# osbee_shield_1_0.net
KiCad netlist of a schematic drawn in EAGLE
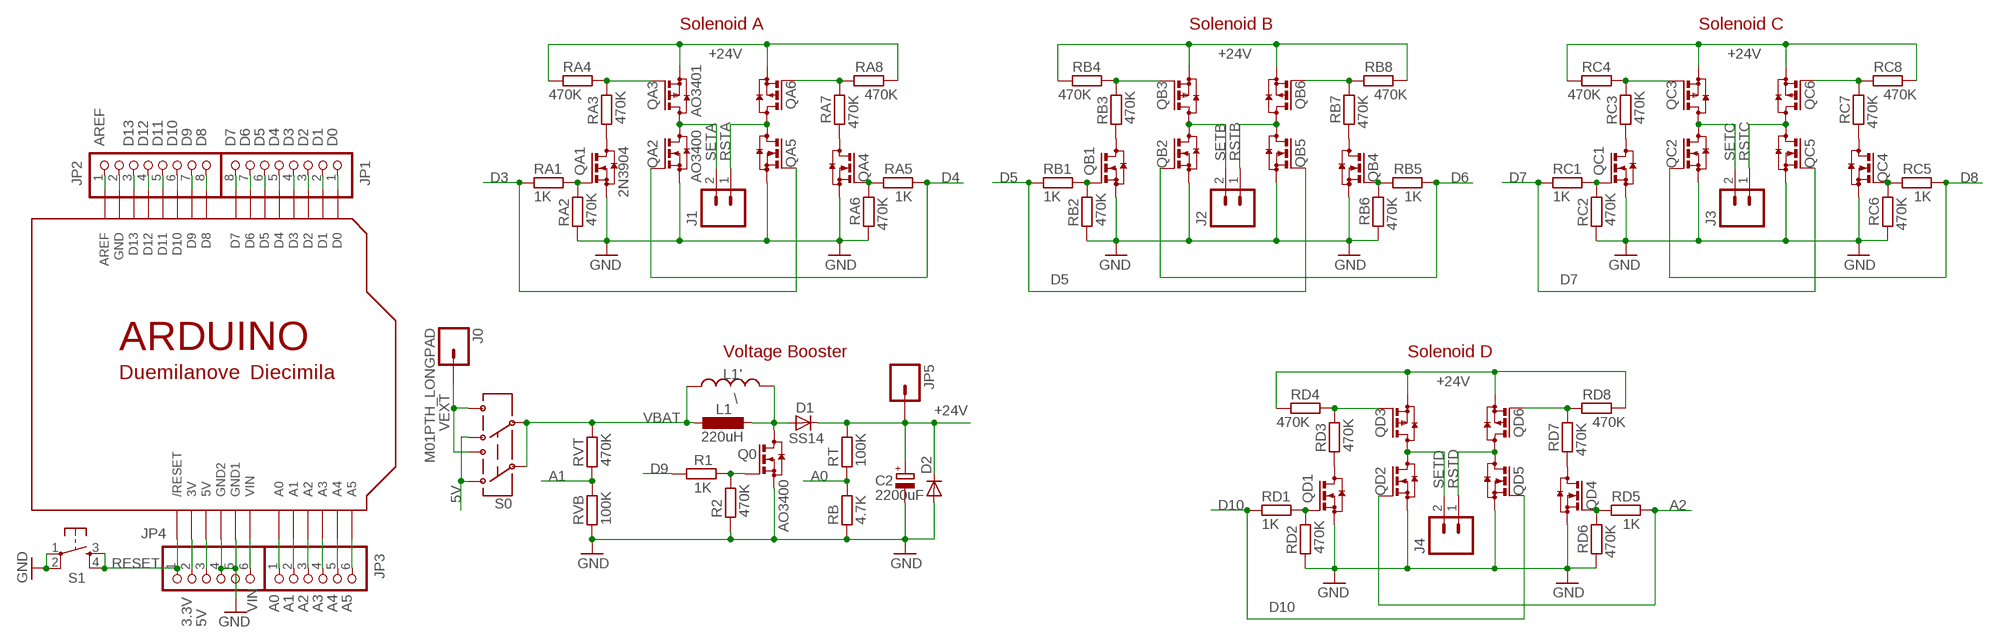
[diagram p0: schematic, sheet 1]

(export (version "E")
  (design (tool "Eeschema 10.0.6"))
  (components
    (comp (ref "C2")
      (value "2200uF")
      (footprint "eagle-import:E5-13")
      (libsource (lib "eagle-import") (part "CPOL-EUE5-13"))
    )
    (comp (ref "D1")
      (value "SS14")
      (footprint "eagle-import:DO-214AC")
      (libsource (lib "eagle-import") (part "DIODE-DO-214AC"))
    )
    (comp (ref "D2")
      (value "DIODE-MINIMELF")
      (footprint "eagle-import:MINIMELF")
      (libsource (lib "eagle-import") (part "DIODE-MINIMELF"))
    )
    (comp (ref "J0")
      (value "M01PTH_LONGPAD")
      (footprint "eagle-import:1X01_LONGPAD")
      (libsource (lib "eagle-import") (part "M01PTH_LONGPAD"))
    )
    (comp (ref "J1")
      (value "M025MM")
      (footprint "eagle-import:SCREWTERMINAL-5MM-2")
      (libsource (lib "eagle-import") (part "M025MM"))
    )
    (comp (ref "J2")
      (value "M025MM")
      (footprint "eagle-import:SCREWTERMINAL-5MM-2")
      (libsource (lib "eagle-import") (part "M025MM"))
    )
    (comp (ref "J3")
      (value "M025MM")
      (footprint "eagle-import:SCREWTERMINAL-5MM-2")
      (libsource (lib "eagle-import") (part "M025MM"))
    )
    (comp (ref "J4")
      (value "M025MM")
      (footprint "eagle-import:SCREWTERMINAL-5MM-2")
      (libsource (lib "eagle-import") (part "M025MM"))
    )
    (comp (ref "JP1")
      (value "PINHD-1X8BIG")
      (footprint "eagle-import:1X08-BIG")
      (libsource (lib "eagle-import") (part "PINHD-1X8BIG"))
    )
    (comp (ref "JP2")
      (value "PINHD-1X8BIG")
      (footprint "eagle-import:1X08-BIG")
      (libsource (lib "eagle-import") (part "PINHD-1X8BIG"))
    )
    (comp (ref "JP3")
      (value "PINHD-1X6B")
      (footprint "eagle-import:1X06-BIG")
      (libsource (lib "eagle-import") (part "PINHD-1X6B"))
    )
    (comp (ref "JP4")
      (value "PINHD-1X6B")
      (footprint "eagle-import:1X06-BIG")
      (libsource (lib "eagle-import") (part "PINHD-1X6B"))
    )
    (comp (ref "JP5")
      (value "M01SMDNS")
      (footprint "eagle-import:1X01NS")
      (libsource (lib "eagle-import") (part "M01SMDNS"))
    )
    (comp (ref "L1")
      (value "220uH")
      (footprint "eagle-import:0204_5")
      (libsource (lib "eagle-import") (part "L-EU0204/5"))
    )
    (comp (ref "L1'")
      (value "\\")
      (footprint "eagle-import:INDUCTOR_D58")
      (libsource (lib "eagle-import") (part "INDUCTOR_SMDD58"))
    )
    (comp (ref "Q0")
      (value "AO3400")
      (footprint "eagle-import:SOT23")
      (libsource (lib "eagle-import") (part "BSS123"))
    )
    (comp (ref "QA1")
      (value "2N3904")
      (footprint "eagle-import:SOT23")
      (libsource (lib "eagle-import") (part "BSS123"))
    )
    (comp (ref "QA2")
      (value "AO3400")
      (footprint "eagle-import:SOT23")
      (libsource (lib "eagle-import") (part "BSS123"))
    )
    (comp (ref "QA3")
      (value "AO3401")
      (footprint "eagle-import:SOT23")
      (libsource (lib "eagle-import") (part "BSS84"))
    )
    (comp (ref "QA4")
      (value "BSS123")
      (footprint "eagle-import:SOT23")
      (libsource (lib "eagle-import") (part "BSS123"))
    )
    (comp (ref "QA5")
      (value "BSS123")
      (footprint "eagle-import:SOT23")
      (libsource (lib "eagle-import") (part "BSS123"))
    )
    (comp (ref "QA6")
      (value "BSS84")
      (footprint "eagle-import:SOT23")
      (libsource (lib "eagle-import") (part "BSS84"))
    )
    (comp (ref "QB1")
      (value "BSS123")
      (footprint "eagle-import:SOT23")
      (libsource (lib "eagle-import") (part "BSS123"))
    )
    (comp (ref "QB2")
      (value "BSS123")
      (footprint "eagle-import:SOT23")
      (libsource (lib "eagle-import") (part "BSS123"))
    )
    (comp (ref "QB3")
      (value "BSS84")
      (footprint "eagle-import:SOT23")
      (libsource (lib "eagle-import") (part "BSS84"))
    )
    (comp (ref "QB4")
      (value "BSS123")
      (footprint "eagle-import:SOT23")
      (libsource (lib "eagle-import") (part "BSS123"))
    )
    (comp (ref "QB5")
      (value "BSS123")
      (footprint "eagle-import:SOT23")
      (libsource (lib "eagle-import") (part "BSS123"))
    )
    (comp (ref "QB6")
      (value "BSS84")
      (footprint "eagle-import:SOT23")
      (libsource (lib "eagle-import") (part "BSS84"))
    )
    (comp (ref "QC1")
      (value "BSS123")
      (footprint "eagle-import:SOT23")
      (libsource (lib "eagle-import") (part "BSS123"))
    )
    (comp (ref "QC2")
      (value "BSS123")
      (footprint "eagle-import:SOT23")
      (libsource (lib "eagle-import") (part "BSS123"))
    )
    (comp (ref "QC3")
      (value "BSS84")
      (footprint "eagle-import:SOT23")
      (libsource (lib "eagle-import") (part "BSS84"))
    )
    (comp (ref "QC4")
      (value "BSS123")
      (footprint "eagle-import:SOT23")
      (libsource (lib "eagle-import") (part "BSS123"))
    )
    (comp (ref "QC5")
      (value "BSS123")
      (footprint "eagle-import:SOT23")
      (libsource (lib "eagle-import") (part "BSS123"))
    )
    (comp (ref "QC6")
      (value "BSS84")
      (footprint "eagle-import:SOT23")
      (libsource (lib "eagle-import") (part "BSS84"))
    )
    (comp (ref "QD1")
      (value "BSS123")
      (footprint "eagle-import:SOT23")
      (libsource (lib "eagle-import") (part "BSS123"))
    )
    (comp (ref "QD2")
      (value "BSS123")
      (footprint "eagle-import:SOT23")
      (libsource (lib "eagle-import") (part "BSS123"))
    )
    (comp (ref "QD3")
      (value "BSS84")
      (footprint "eagle-import:SOT23")
      (libsource (lib "eagle-import") (part "BSS84"))
    )
    (comp (ref "QD4")
      (value "BSS123")
      (footprint "eagle-import:SOT23")
      (libsource (lib "eagle-import") (part "BSS123"))
    )
    (comp (ref "QD5")
      (value "BSS123")
      (footprint "eagle-import:SOT23")
      (libsource (lib "eagle-import") (part "BSS123"))
    )
    (comp (ref "QD6")
      (value "BSS84")
      (footprint "eagle-import:SOT23")
      (libsource (lib "eagle-import") (part "BSS84"))
    )
    (comp (ref "R1")
      (value "1K")
      (footprint "eagle-import:R0805")
      (libsource (lib "eagle-import") (part "R-EU_R0805"))
    )
    (comp (ref "R2")
      (value "470K")
      (footprint "eagle-import:R0805")
      (libsource (lib "eagle-import") (part "R-EU_R0805"))
    )
    (comp (ref "RA1")
      (value "1K")
      (footprint "eagle-import:R0805")
      (libsource (lib "eagle-import") (part "R-EU_R0805"))
    )
    (comp (ref "RA2")
      (value "470K")
      (footprint "eagle-import:R0805")
      (libsource (lib "eagle-import") (part "R-EU_R0805"))
    )
    (comp (ref "RA3")
      (value "470K")
      (footprint "eagle-import:R0805")
      (libsource (lib "eagle-import") (part "R-EU_R0805"))
    )
    (comp (ref "RA4")
      (value "470K")
      (footprint "eagle-import:R0805")
      (libsource (lib "eagle-import") (part "R-EU_R0805"))
    )
    (comp (ref "RA5")
      (value "1K")
      (footprint "eagle-import:R0805")
      (libsource (lib "eagle-import") (part "R-EU_R0805"))
    )
    (comp (ref "RA6")
      (value "470K")
      (footprint "eagle-import:R0805")
      (libsource (lib "eagle-import") (part "R-EU_R0805"))
    )
    (comp (ref "RA7")
      (value "470K")
      (footprint "eagle-import:R0805")
      (libsource (lib "eagle-import") (part "R-EU_R0805"))
    )
    (comp (ref "RA8")
      (value "470K")
      (footprint "eagle-import:R0805")
      (libsource (lib "eagle-import") (part "R-EU_R0805"))
    )
    (comp (ref "RB")
      (value "4.7K")
      (footprint "eagle-import:R0805")
      (libsource (lib "eagle-import") (part "R-EU_R0805"))
    )
    (comp (ref "RB1")
      (value "1K")
      (footprint "eagle-import:R0805")
      (libsource (lib "eagle-import") (part "R-EU_R0805"))
    )
    (comp (ref "RB2")
      (value "470K")
      (footprint "eagle-import:R0805")
      (libsource (lib "eagle-import") (part "R-EU_R0805"))
    )
    (comp (ref "RB3")
      (value "470K")
      (footprint "eagle-import:R0805")
      (libsource (lib "eagle-import") (part "R-EU_R0805"))
    )
    (comp (ref "RB4")
      (value "470K")
      (footprint "eagle-import:R0805")
      (libsource (lib "eagle-import") (part "R-EU_R0805"))
    )
    (comp (ref "RB5")
      (value "1K")
      (footprint "eagle-import:R0805")
      (libsource (lib "eagle-import") (part "R-EU_R0805"))
    )
    (comp (ref "RB6")
      (value "470K")
      (footprint "eagle-import:R0805")
      (libsource (lib "eagle-import") (part "R-EU_R0805"))
    )
    (comp (ref "RB7")
      (value "470K")
      (footprint "eagle-import:R0805")
      (libsource (lib "eagle-import") (part "R-EU_R0805"))
    )
    (comp (ref "RB8")
      (value "470K")
      (footprint "eagle-import:R0805")
      (libsource (lib "eagle-import") (part "R-EU_R0805"))
    )
    (comp (ref "RC1")
      (value "1K")
      (footprint "eagle-import:R0805")
      (libsource (lib "eagle-import") (part "R-EU_R0805"))
    )
    (comp (ref "RC2")
      (value "470K")
      (footprint "eagle-import:R0805")
      (libsource (lib "eagle-import") (part "R-EU_R0805"))
    )
    (comp (ref "RC3")
      (value "470K")
      (footprint "eagle-import:R0805")
      (libsource (lib "eagle-import") (part "R-EU_R0805"))
    )
    (comp (ref "RC4")
      (value "470K")
      (footprint "eagle-import:R0805")
      (libsource (lib "eagle-import") (part "R-EU_R0805"))
    )
    (comp (ref "RC5")
      (value "1K")
      (footprint "eagle-import:R0805")
      (libsource (lib "eagle-import") (part "R-EU_R0805"))
    )
    (comp (ref "RC6")
      (value "470K")
      (footprint "eagle-import:R0805")
      (libsource (lib "eagle-import") (part "R-EU_R0805"))
    )
    (comp (ref "RC7")
      (value "470K")
      (footprint "eagle-import:R0805")
      (libsource (lib "eagle-import") (part "R-EU_R0805"))
    )
    (comp (ref "RC8")
      (value "470K")
      (footprint "eagle-import:R0805")
      (libsource (lib "eagle-import") (part "R-EU_R0805"))
    )
    (comp (ref "RD1")
      (value "1K")
      (footprint "eagle-import:R0805")
      (libsource (lib "eagle-import") (part "R-EU_R0805"))
    )
    (comp (ref "RD2")
      (value "470K")
      (footprint "eagle-import:R0805")
      (libsource (lib "eagle-import") (part "R-EU_R0805"))
    )
    (comp (ref "RD3")
      (value "470K")
      (footprint "eagle-import:R0805")
      (libsource (lib "eagle-import") (part "R-EU_R0805"))
    )
    (comp (ref "RD4")
      (value "470K")
      (footprint "eagle-import:R0805")
      (libsource (lib "eagle-import") (part "R-EU_R0805"))
    )
    (comp (ref "RD5")
      (value "1K")
      (footprint "eagle-import:R0805")
      (libsource (lib "eagle-import") (part "R-EU_R0805"))
    )
    (comp (ref "RD6")
      (value "470K")
      (footprint "eagle-import:R0805")
      (libsource (lib "eagle-import") (part "R-EU_R0805"))
    )
    (comp (ref "RD7")
      (value "470K")
      (footprint "eagle-import:R0805")
      (libsource (lib "eagle-import") (part "R-EU_R0805"))
    )
    (comp (ref "RD8")
      (value "470K")
      (footprint "eagle-import:R0805")
      (libsource (lib "eagle-import") (part "R-EU_R0805"))
    )
    (comp (ref "RT")
      (value "100K")
      (footprint "eagle-import:R0805")
      (libsource (lib "eagle-import") (part "R-EU_R0805"))
    )
    (comp (ref "RVB")
      (value "100K")
      (footprint "eagle-import:R0805")
      (libsource (lib "eagle-import") (part "R-EU_R0805"))
    )
    (comp (ref "RVT")
      (value "470K")
      (footprint "eagle-import:R0805")
      (libsource (lib "eagle-import") (part "R-EU_R0805"))
    )
    (comp (ref "S0")
      (value "AYZ0202")
      (footprint "eagle-import:AYZ0202")
      (libsource (lib "eagle-import") (part "AYZ0202"))
    )
    (comp (ref "S1")
      (value "TAC_SWITCHPTH")
      (footprint "eagle-import:TACTILE-PTH")
      (libsource (lib "eagle-import") (part "TAC_SWITCHPTH"))
    )
    (comp (ref "U$1")
      (value "ARDUINODUEMILANOVE-NODIM")
      (footprint "eagle-import:ARDUINO-NODIM")
      (libsource (lib "eagle-import") (part "ARDUINODUEMILANOVE-NODIM"))
    )
  )
  (nets
    (net (code "1") (name "/+24V") (class "Default")
      (node (ref "C2") (pin "+") (pinfunction "+_+") (pintype "passive"))
      (node (ref "D1") (pin "C") (pinfunction "C_C") (pintype "passive"))
      (node (ref "D2") (pin "C") (pinfunction "C_C") (pintype "passive"))
      (node (ref "JP5") (pin "1") (pinfunction "1_1") (pintype "passive"))
      (node (ref "QA3") (pin "2") (pinfunction "S_2") (pintype "passive"))
      (node (ref "QA6") (pin "2") (pinfunction "S_2") (pintype "passive"))
      (node (ref "QB3") (pin "2") (pinfunction "S_2") (pintype "passive"))
      (node (ref "QB6") (pin "2") (pinfunction "S_2") (pintype "passive"))
      (node (ref "QC3") (pin "2") (pinfunction "S_2") (pintype "passive"))
      (node (ref "QC6") (pin "2") (pinfunction "S_2") (pintype "passive"))
      (node (ref "QD3") (pin "2") (pinfunction "S_2") (pintype "passive"))
      (node (ref "QD6") (pin "2") (pinfunction "S_2") (pintype "passive"))
      (node (ref "RA4") (pin "2") (pinfunction "2_2") (pintype "passive"))
      (node (ref "RA8") (pin "2") (pinfunction "2_2") (pintype "passive"))
      (node (ref "RB4") (pin "2") (pinfunction "2_2") (pintype "passive"))
      (node (ref "RB8") (pin "2") (pinfunction "2_2") (pintype "passive"))
      (node (ref "RC4") (pin "2") (pinfunction "2_2") (pintype "passive"))
      (node (ref "RC8") (pin "2") (pinfunction "2_2") (pintype "passive"))
      (node (ref "RD4") (pin "2") (pinfunction "2_2") (pintype "passive"))
      (node (ref "RD8") (pin "2") (pinfunction "2_2") (pintype "passive"))
      (node (ref "RT") (pin "2") (pinfunction "2_2") (pintype "passive"))
    )
    (net (code "2") (name "/3.3V") (class "Default")
      (node (ref "JP4") (pin "2") (pinfunction "2_2") (pintype "passive"))
      (node (ref "U$1") (pin "3V") (pinfunction "3V_3V") (pintype "power_in"))
    )
    (net (code "3") (name "/5V") (class "Default")
      (node (ref "JP4") (pin "3") (pinfunction "3_3") (pintype "passive"))
      (node (ref "S0") (pin "3") (pinfunction "1_3") (pintype "bidirectional"))
      (node (ref "S0") (pin "6") (pinfunction "4_6") (pintype "bidirectional"))
      (node (ref "U$1") (pin "5V") (pinfunction "5V_5V") (pintype "power_in"))
    )
    (net (code "4") (name "/A0") (class "Default")
      (node (ref "JP3") (pin "1") (pinfunction "1_1") (pintype "passive"))
      (node (ref "RB") (pin "2") (pinfunction "2_2") (pintype "passive"))
      (node (ref "RT") (pin "1") (pinfunction "1_1") (pintype "passive"))
      (node (ref "U$1") (pin "A0") (pinfunction "A0_A0") (pintype "bidirectional"))
    )
    (net (code "5") (name "/A1") (class "Default")
      (node (ref "JP3") (pin "2") (pinfunction "2_2") (pintype "passive"))
      (node (ref "RVB") (pin "2") (pinfunction "2_2") (pintype "passive"))
      (node (ref "RVT") (pin "1") (pinfunction "1_1") (pintype "passive"))
      (node (ref "U$1") (pin "A1") (pinfunction "A1_A1") (pintype "bidirectional"))
    )
    (net (code "6") (name "/A2") (class "Default")
      (node (ref "JP3") (pin "3") (pinfunction "3_3") (pintype "passive"))
      (node (ref "QD2") (pin "1") (pinfunction "G_1") (pintype "passive"))
      (node (ref "RD5") (pin "1") (pinfunction "1_1") (pintype "passive"))
      (node (ref "U$1") (pin "A2") (pinfunction "A2_A2") (pintype "bidirectional"))
    )
    (net (code "7") (name "/A3") (class "Default")
      (node (ref "JP3") (pin "4") (pinfunction "4_4") (pintype "passive"))
      (node (ref "U$1") (pin "A3") (pinfunction "A3_A3") (pintype "bidirectional"))
    )
    (net (code "8") (name "/A4") (class "Default")
      (node (ref "JP3") (pin "5") (pinfunction "5_5") (pintype "passive"))
      (node (ref "U$1") (pin "A4") (pinfunction "A4_A4") (pintype "bidirectional"))
    )
    (net (code "9") (name "/A5") (class "Default")
      (node (ref "JP3") (pin "6") (pinfunction "6_6") (pintype "passive"))
      (node (ref "U$1") (pin "A5") (pinfunction "A5_A5") (pintype "bidirectional"))
    )
    (net (code "10") (name "/AREF") (class "Default")
      (node (ref "JP2") (pin "1") (pinfunction "1_1") (pintype "passive"))
      (node (ref "U$1") (pin "AREF") (pinfunction "AREF_AREF") (pintype "bidirectional"))
    )
    (net (code "11") (name "/D0") (class "Default")
      (node (ref "JP1") (pin "1") (pinfunction "1_1") (pintype "passive"))
      (node (ref "U$1") (pin "D0") (pinfunction "D0_D0") (pintype "bidirectional"))
    )
    (net (code "12") (name "/D1") (class "Default")
      (node (ref "JP1") (pin "2") (pinfunction "2_2") (pintype "passive"))
      (node (ref "U$1") (pin "D1") (pinfunction "D1_D1") (pintype "bidirectional"))
    )
    (net (code "13") (name "/D2") (class "Default")
      (node (ref "JP1") (pin "3") (pinfunction "3_3") (pintype "passive"))
      (node (ref "U$1") (pin "D2") (pinfunction "D2_D2") (pintype "bidirectional"))
    )
    (net (code "14") (name "/D3") (class "Default")
      (node (ref "JP1") (pin "4") (pinfunction "4_4") (pintype "passive"))
      (node (ref "QA5") (pin "1") (pinfunction "G_1") (pintype "passive"))
      (node (ref "RA1") (pin "1") (pinfunction "1_1") (pintype "passive"))
      (node (ref "U$1") (pin "D3") (pinfunction "D3_D3") (pintype "bidirectional"))
    )
    (net (code "15") (name "/D4") (class "Default")
      (node (ref "JP1") (pin "5") (pinfunction "5_5") (pintype "passive"))
      (node (ref "QA2") (pin "1") (pinfunction "G_1") (pintype "passive"))
      (node (ref "RA5") (pin "1") (pinfunction "1_1") (pintype "passive"))
      (node (ref "U$1") (pin "D4") (pinfunction "D4_D4") (pintype "bidirectional"))
    )
    (net (code "16") (name "/D5") (class "Default")
      (node (ref "JP1") (pin "6") (pinfunction "6_6") (pintype "passive"))
      (node (ref "QB5") (pin "1") (pinfunction "G_1") (pintype "passive"))
      (node (ref "RB1") (pin "1") (pinfunction "1_1") (pintype "passive"))
      (node (ref "U$1") (pin "D5") (pinfunction "D5_D5") (pintype "bidirectional"))
    )
    (net (code "17") (name "/D6") (class "Default")
      (node (ref "JP1") (pin "7") (pinfunction "7_7") (pintype "passive"))
      (node (ref "QB2") (pin "1") (pinfunction "G_1") (pintype "passive"))
      (node (ref "RB5") (pin "1") (pinfunction "1_1") (pintype "passive"))
      (node (ref "U$1") (pin "D6") (pinfunction "D6_D6") (pintype "bidirectional"))
    )
    (net (code "18") (name "/D7") (class "Default")
      (node (ref "JP1") (pin "8") (pinfunction "8_8") (pintype "passive"))
      (node (ref "QC5") (pin "1") (pinfunction "G_1") (pintype "passive"))
      (node (ref "RC1") (pin "1") (pinfunction "1_1") (pintype "passive"))
      (node (ref "U$1") (pin "D7") (pinfunction "D7_D7") (pintype "bidirectional"))
    )
    (net (code "19") (name "/D8") (class "Default")
      (node (ref "JP2") (pin "8") (pinfunction "8_8") (pintype "passive"))
      (node (ref "QC2") (pin "1") (pinfunction "G_1") (pintype "passive"))
      (node (ref "RC5") (pin "1") (pinfunction "1_1") (pintype "passive"))
      (node (ref "U$1") (pin "D8") (pinfunction "D8_D8") (pintype "bidirectional"))
    )
    (net (code "20") (name "/D9") (class "Default")
      (node (ref "JP2") (pin "7") (pinfunction "7_7") (pintype "passive"))
      (node (ref "R1") (pin "2") (pinfunction "2_2") (pintype "passive"))
      (node (ref "U$1") (pin "D9") (pinfunction "D9_D9") (pintype "bidirectional"))
    )
    (net (code "21") (name "/D10") (class "Default")
      (node (ref "JP2") (pin "6") (pinfunction "6_6") (pintype "passive"))
      (node (ref "QD5") (pin "1") (pinfunction "G_1") (pintype "passive"))
      (node (ref "RD1") (pin "1") (pinfunction "1_1") (pintype "passive"))
      (node (ref "U$1") (pin "D10") (pinfunction "D10_D10") (pintype "bidirectional"))
    )
    (net (code "22") (name "/D11") (class "Default")
      (node (ref "JP2") (pin "5") (pinfunction "5_5") (pintype "passive"))
      (node (ref "U$1") (pin "D11") (pinfunction "D11_D11") (pintype "bidirectional"))
    )
    (net (code "23") (name "/D12") (class "Default")
      (node (ref "JP2") (pin "4") (pinfunction "4_4") (pintype "passive"))
      (node (ref "U$1") (pin "D12") (pinfunction "D12_D12") (pintype "bidirectional"))
    )
    (net (code "24") (name "/D13") (class "Default")
      (node (ref "JP2") (pin "3") (pinfunction "3_3") (pintype "passive"))
      (node (ref "U$1") (pin "D13") (pinfunction "D13_D13") (pintype "bidirectional"))
    )
    (net (code "25") (name "/RESET") (class "Default")
      (node (ref "JP4") (pin "1") (pinfunction "1_1") (pintype "passive"))
      (node (ref "S1") (pin "3") (pinfunction "3_3") (pintype "passive"))
      (node (ref "S1") (pin "4") (pinfunction "4_4") (pintype "passive"))
      (node (ref "U$1") (pin "RESET") (pinfunction "/RESET_RESET") (pintype "bidirectional"))
    )
    (net (code "26") (name "/RSTA") (class "Default")
      (node (ref "J1") (pin "1") (pinfunction "1_1") (pintype "passive"))
      (node (ref "QA5") (pin "3") (pinfunction "D_3") (pintype "passive"))
      (node (ref "QA6") (pin "3") (pinfunction "D_3") (pintype "passive"))
    )
    (net (code "27") (name "/RSTB") (class "Default")
      (node (ref "J2") (pin "1") (pinfunction "1_1") (pintype "passive"))
      (node (ref "QB5") (pin "3") (pinfunction "D_3") (pintype "passive"))
      (node (ref "QB6") (pin "3") (pinfunction "D_3") (pintype "passive"))
    )
    (net (code "28") (name "/RSTC") (class "Default")
      (node (ref "J3") (pin "1") (pinfunction "1_1") (pintype "passive"))
      (node (ref "QC5") (pin "3") (pinfunction "D_3") (pintype "passive"))
      (node (ref "QC6") (pin "3") (pinfunction "D_3") (pintype "passive"))
    )
    (net (code "29") (name "/RSTD") (class "Default")
      (node (ref "J4") (pin "1") (pinfunction "1_1") (pintype "passive"))
      (node (ref "QD5") (pin "3") (pinfunction "D_3") (pintype "passive"))
      (node (ref "QD6") (pin "3") (pinfunction "D_3") (pintype "passive"))
    )
    (net (code "30") (name "/SETA") (class "Default")
      (node (ref "J1") (pin "2") (pinfunction "2_2") (pintype "passive"))
      (node (ref "QA2") (pin "3") (pinfunction "D_3") (pintype "passive"))
      (node (ref "QA3") (pin "3") (pinfunction "D_3") (pintype "passive"))
    )
    (net (code "31") (name "/SETB") (class "Default")
      (node (ref "J2") (pin "2") (pinfunction "2_2") (pintype "passive"))
      (node (ref "QB2") (pin "3") (pinfunction "D_3") (pintype "passive"))
      (node (ref "QB3") (pin "3") (pinfunction "D_3") (pintype "passive"))
    )
    (net (code "32") (name "/SETC") (class "Default")
      (node (ref "J3") (pin "2") (pinfunction "2_2") (pintype "passive"))
      (node (ref "QC2") (pin "3") (pinfunction "D_3") (pintype "passive"))
      (node (ref "QC3") (pin "3") (pinfunction "D_3") (pintype "passive"))
    )
    (net (code "33") (name "/SETD") (class "Default")
      (node (ref "J4") (pin "2") (pinfunction "2_2") (pintype "passive"))
      (node (ref "QD2") (pin "3") (pinfunction "D_3") (pintype "passive"))
      (node (ref "QD3") (pin "3") (pinfunction "D_3") (pintype "passive"))
    )
    (net (code "34") (name "/VBAT") (class "Default")
      (node (ref "L1") (pin "1") (pinfunction "1_1") (pintype "passive"))
      (node (ref "L1'") (pin "P$1") (pinfunction "1_P$1") (pintype "passive"))
      (node (ref "RVT") (pin "2") (pinfunction "2_2") (pintype "passive"))
      (node (ref "S0") (pin "2") (pinfunction "2_2") (pintype "bidirectional"))
      (node (ref "S0") (pin "5") (pinfunction "5_5") (pintype "bidirectional"))
    )
    (net (code "35") (name "/VEXT") (class "Default")
      (node (ref "J0") (pin "1") (pinfunction "1_1") (pintype "passive"))
      (node (ref "S0") (pin "1") (pinfunction "3_1") (pintype "bidirectional"))
      (node (ref "S0") (pin "4") (pinfunction "6_4") (pintype "bidirectional"))
    )
    (net (code "36") (name "/VIN") (class "Default")
      (node (ref "JP4") (pin "6") (pinfunction "6_6") (pintype "passive"))
      (node (ref "U$1") (pin "VIN") (pinfunction "VIN_VIN") (pintype "power_in"))
    )
    (net (code "37") (name "GND") (class "Default")
      (node (ref "C2") (pin "-") (pinfunction "-_-") (pintype "passive"))
      (node (ref "D2") (pin "A") (pinfunction "A_A") (pintype "passive"))
      (node (ref "JP4") (pin "4") (pinfunction "4_4") (pintype "passive"))
      (node (ref "JP4") (pin "5") (pinfunction "5_5") (pintype "passive"))
      (node (ref "Q0") (pin "2") (pinfunction "S_2") (pintype "passive"))
      (node (ref "QA1") (pin "2") (pinfunction "S_2") (pintype "passive"))
      (node (ref "QA2") (pin "2") (pinfunction "S_2") (pintype "passive"))
      (node (ref "QA4") (pin "2") (pinfunction "S_2") (pintype "passive"))
      (node (ref "QA5") (pin "2") (pinfunction "S_2") (pintype "passive"))
      (node (ref "QB1") (pin "2") (pinfunction "S_2") (pintype "passive"))
      (node (ref "QB2") (pin "2") (pinfunction "S_2") (pintype "passive"))
      (node (ref "QB4") (pin "2") (pinfunction "S_2") (pintype "passive"))
      (node (ref "QB5") (pin "2") (pinfunction "S_2") (pintype "passive"))
      (node (ref "QC1") (pin "2") (pinfunction "S_2") (pintype "passive"))
      (node (ref "QC2") (pin "2") (pinfunction "S_2") (pintype "passive"))
      (node (ref "QC4") (pin "2") (pinfunction "S_2") (pintype "passive"))
      (node (ref "QC5") (pin "2") (pinfunction "S_2") (pintype "passive"))
      (node (ref "QD1") (pin "2") (pinfunction "S_2") (pintype "passive"))
      (node (ref "QD2") (pin "2") (pinfunction "S_2") (pintype "passive"))
      (node (ref "QD4") (pin "2") (pinfunction "S_2") (pintype "passive"))
      (node (ref "QD5") (pin "2") (pinfunction "S_2") (pintype "passive"))
      (node (ref "R2") (pin "1") (pinfunction "1_1") (pintype "passive"))
      (node (ref "RA2") (pin "1") (pinfunction "1_1") (pintype "passive"))
      (node (ref "RA6") (pin "1") (pinfunction "1_1") (pintype "passive"))
      (node (ref "RB") (pin "1") (pinfunction "1_1") (pintype "passive"))
      (node (ref "RB2") (pin "1") (pinfunction "1_1") (pintype "passive"))
      (node (ref "RB6") (pin "1") (pinfunction "1_1") (pintype "passive"))
      (node (ref "RC2") (pin "1") (pinfunction "1_1") (pintype "passive"))
      (node (ref "RC6") (pin "1") (pinfunction "1_1") (pintype "passive"))
      (node (ref "RD2") (pin "1") (pinfunction "1_1") (pintype "passive"))
      (node (ref "RD6") (pin "1") (pinfunction "1_1") (pintype "passive"))
      (node (ref "RVB") (pin "1") (pinfunction "1_1") (pintype "passive"))
      (node (ref "S1") (pin "1") (pinfunction "1_1") (pintype "passive"))
      (node (ref "S1") (pin "2") (pinfunction "2_2") (pintype "passive"))
      (node (ref "U$1") (pin "GND1") (pinfunction "GND1_GND1") (pintype "power_in"))
      (node (ref "U$1") (pin "GND2") (pinfunction "GND2_GND2") (pintype "power_in"))
    )
    (net (code "38") (name "Net-(JP2-Pad2)") (class "Default")
      (node (ref "JP2") (pin "2") (pinfunction "2_2") (pintype "passive"))
      (node (ref "U$1") (pin "GND") (pinfunction "GND_GND") (pintype "power_in"))
    )
    (net (code "39") (name "Net-(L1'-2)") (class "Default")
      (node (ref "D1") (pin "A") (pinfunction "A_A") (pintype "passive"))
      (node (ref "L1") (pin "2") (pinfunction "2_2") (pintype "passive"))
      (node (ref "L1'") (pin "P$2") (pinfunction "2_P$2") (pintype "passive"))
      (node (ref "Q0") (pin "3") (pinfunction "D_3") (pintype "passive"))
    )
    (net (code "40") (name "Net-(Q0-G)") (class "Default")
      (node (ref "Q0") (pin "1") (pinfunction "G_1") (pintype "passive"))
      (node (ref "R1") (pin "1") (pinfunction "1_1") (pintype "passive"))
      (node (ref "R2") (pin "2") (pinfunction "2_2") (pintype "passive"))
    )
    (net (code "41") (name "Net-(QA1-D)") (class "Default")
      (node (ref "QA1") (pin "3") (pinfunction "D_3") (pintype "passive"))
      (node (ref "RA3") (pin "1") (pinfunction "1_1") (pintype "passive"))
    )
    (net (code "42") (name "Net-(QA1-G)") (class "Default")
      (node (ref "QA1") (pin "1") (pinfunction "G_1") (pintype "passive"))
      (node (ref "RA1") (pin "2") (pinfunction "2_2") (pintype "passive"))
      (node (ref "RA2") (pin "2") (pinfunction "2_2") (pintype "passive"))
    )
    (net (code "43") (name "Net-(QA3-G)") (class "Default")
      (node (ref "QA3") (pin "1") (pinfunction "G_1") (pintype "passive"))
      (node (ref "RA3") (pin "2") (pinfunction "2_2") (pintype "passive"))
      (node (ref "RA4") (pin "1") (pinfunction "1_1") (pintype "passive"))
    )
    (net (code "44") (name "Net-(QA4-D)") (class "Default")
      (node (ref "QA4") (pin "3") (pinfunction "D_3") (pintype "passive"))
      (node (ref "RA7") (pin "1") (pinfunction "1_1") (pintype "passive"))
    )
    (net (code "45") (name "Net-(QA4-G)") (class "Default")
      (node (ref "QA4") (pin "1") (pinfunction "G_1") (pintype "passive"))
      (node (ref "RA5") (pin "2") (pinfunction "2_2") (pintype "passive"))
      (node (ref "RA6") (pin "2") (pinfunction "2_2") (pintype "passive"))
    )
    (net (code "46") (name "Net-(QA6-G)") (class "Default")
      (node (ref "QA6") (pin "1") (pinfunction "G_1") (pintype "passive"))
      (node (ref "RA7") (pin "2") (pinfunction "2_2") (pintype "passive"))
      (node (ref "RA8") (pin "1") (pinfunction "1_1") (pintype "passive"))
    )
    (net (code "47") (name "Net-(QB1-D)") (class "Default")
      (node (ref "QB1") (pin "3") (pinfunction "D_3") (pintype "passive"))
      (node (ref "RB3") (pin "1") (pinfunction "1_1") (pintype "passive"))
    )
    (net (code "48") (name "Net-(QB1-G)") (class "Default")
      (node (ref "QB1") (pin "1") (pinfunction "G_1") (pintype "passive"))
      (node (ref "RB1") (pin "2") (pinfunction "2_2") (pintype "passive"))
      (node (ref "RB2") (pin "2") (pinfunction "2_2") (pintype "passive"))
    )
    (net (code "49") (name "Net-(QB3-G)") (class "Default")
      (node (ref "QB3") (pin "1") (pinfunction "G_1") (pintype "passive"))
      (node (ref "RB3") (pin "2") (pinfunction "2_2") (pintype "passive"))
      (node (ref "RB4") (pin "1") (pinfunction "1_1") (pintype "passive"))
    )
    (net (code "50") (name "Net-(QB4-D)") (class "Default")
      (node (ref "QB4") (pin "3") (pinfunction "D_3") (pintype "passive"))
      (node (ref "RB7") (pin "1") (pinfunction "1_1") (pintype "passive"))
    )
    (net (code "51") (name "Net-(QB4-G)") (class "Default")
      (node (ref "QB4") (pin "1") (pinfunction "G_1") (pintype "passive"))
      (node (ref "RB5") (pin "2") (pinfunction "2_2") (pintype "passive"))
      (node (ref "RB6") (pin "2") (pinfunction "2_2") (pintype "passive"))
    )
    (net (code "52") (name "Net-(QB6-G)") (class "Default")
      (node (ref "QB6") (pin "1") (pinfunction "G_1") (pintype "passive"))
      (node (ref "RB7") (pin "2") (pinfunction "2_2") (pintype "passive"))
      (node (ref "RB8") (pin "1") (pinfunction "1_1") (pintype "passive"))
    )
    (net (code "53") (name "Net-(QC1-D)") (class "Default")
      (node (ref "QC1") (pin "3") (pinfunction "D_3") (pintype "passive"))
      (node (ref "RC3") (pin "1") (pinfunction "1_1") (pintype "passive"))
    )
    (net (code "54") (name "Net-(QC1-G)") (class "Default")
      (node (ref "QC1") (pin "1") (pinfunction "G_1") (pintype "passive"))
      (node (ref "RC1") (pin "2") (pinfunction "2_2") (pintype "passive"))
      (node (ref "RC2") (pin "2") (pinfunction "2_2") (pintype "passive"))
    )
    (net (code "55") (name "Net-(QC3-G)") (class "Default")
      (node (ref "QC3") (pin "1") (pinfunction "G_1") (pintype "passive"))
      (node (ref "RC3") (pin "2") (pinfunction "2_2") (pintype "passive"))
      (node (ref "RC4") (pin "1") (pinfunction "1_1") (pintype "passive"))
    )
    (net (code "56") (name "Net-(QC4-D)") (class "Default")
      (node (ref "QC4") (pin "3") (pinfunction "D_3") (pintype "passive"))
      (node (ref "RC7") (pin "1") (pinfunction "1_1") (pintype "passive"))
    )
    (net (code "57") (name "Net-(QC4-G)") (class "Default")
      (node (ref "QC4") (pin "1") (pinfunction "G_1") (pintype "passive"))
      (node (ref "RC5") (pin "2") (pinfunction "2_2") (pintype "passive"))
      (node (ref "RC6") (pin "2") (pinfunction "2_2") (pintype "passive"))
    )
    (net (code "58") (name "Net-(QC6-G)") (class "Default")
      (node (ref "QC6") (pin "1") (pinfunction "G_1") (pintype "passive"))
      (node (ref "RC7") (pin "2") (pinfunction "2_2") (pintype "passive"))
      (node (ref "RC8") (pin "1") (pinfunction "1_1") (pintype "passive"))
    )
    (net (code "59") (name "Net-(QD1-D)") (class "Default")
      (node (ref "QD1") (pin "3") (pinfunction "D_3") (pintype "passive"))
      (node (ref "RD3") (pin "1") (pinfunction "1_1") (pintype "passive"))
    )
    (net (code "60") (name "Net-(QD1-G)") (class "Default")
      (node (ref "QD1") (pin "1") (pinfunction "G_1") (pintype "passive"))
      (node (ref "RD1") (pin "2") (pinfunction "2_2") (pintype "passive"))
      (node (ref "RD2") (pin "2") (pinfunction "2_2") (pintype "passive"))
    )
    (net (code "61") (name "Net-(QD3-G)") (class "Default")
      (node (ref "QD3") (pin "1") (pinfunction "G_1") (pintype "passive"))
      (node (ref "RD3") (pin "2") (pinfunction "2_2") (pintype "passive"))
      (node (ref "RD4") (pin "1") (pinfunction "1_1") (pintype "passive"))
    )
    (net (code "62") (name "Net-(QD4-D)") (class "Default")
      (node (ref "QD4") (pin "3") (pinfunction "D_3") (pintype "passive"))
      (node (ref "RD7") (pin "1") (pinfunction "1_1") (pintype "passive"))
    )
    (net (code "63") (name "Net-(QD4-G)") (class "Default")
      (node (ref "QD4") (pin "1") (pinfunction "G_1") (pintype "passive"))
      (node (ref "RD5") (pin "2") (pinfunction "2_2") (pintype "passive"))
      (node (ref "RD6") (pin "2") (pinfunction "2_2") (pintype "passive"))
    )
    (net (code "64") (name "Net-(QD6-G)") (class "Default")
      (node (ref "QD6") (pin "1") (pinfunction "G_1") (pintype "passive"))
      (node (ref "RD7") (pin "2") (pinfunction "2_2") (pintype "passive"))
      (node (ref "RD8") (pin "1") (pinfunction "1_1") (pintype "passive"))
    )
  )
)
